# Duckietown_2018B.net
KiCad netlist of a schematic drawn in EAGLE
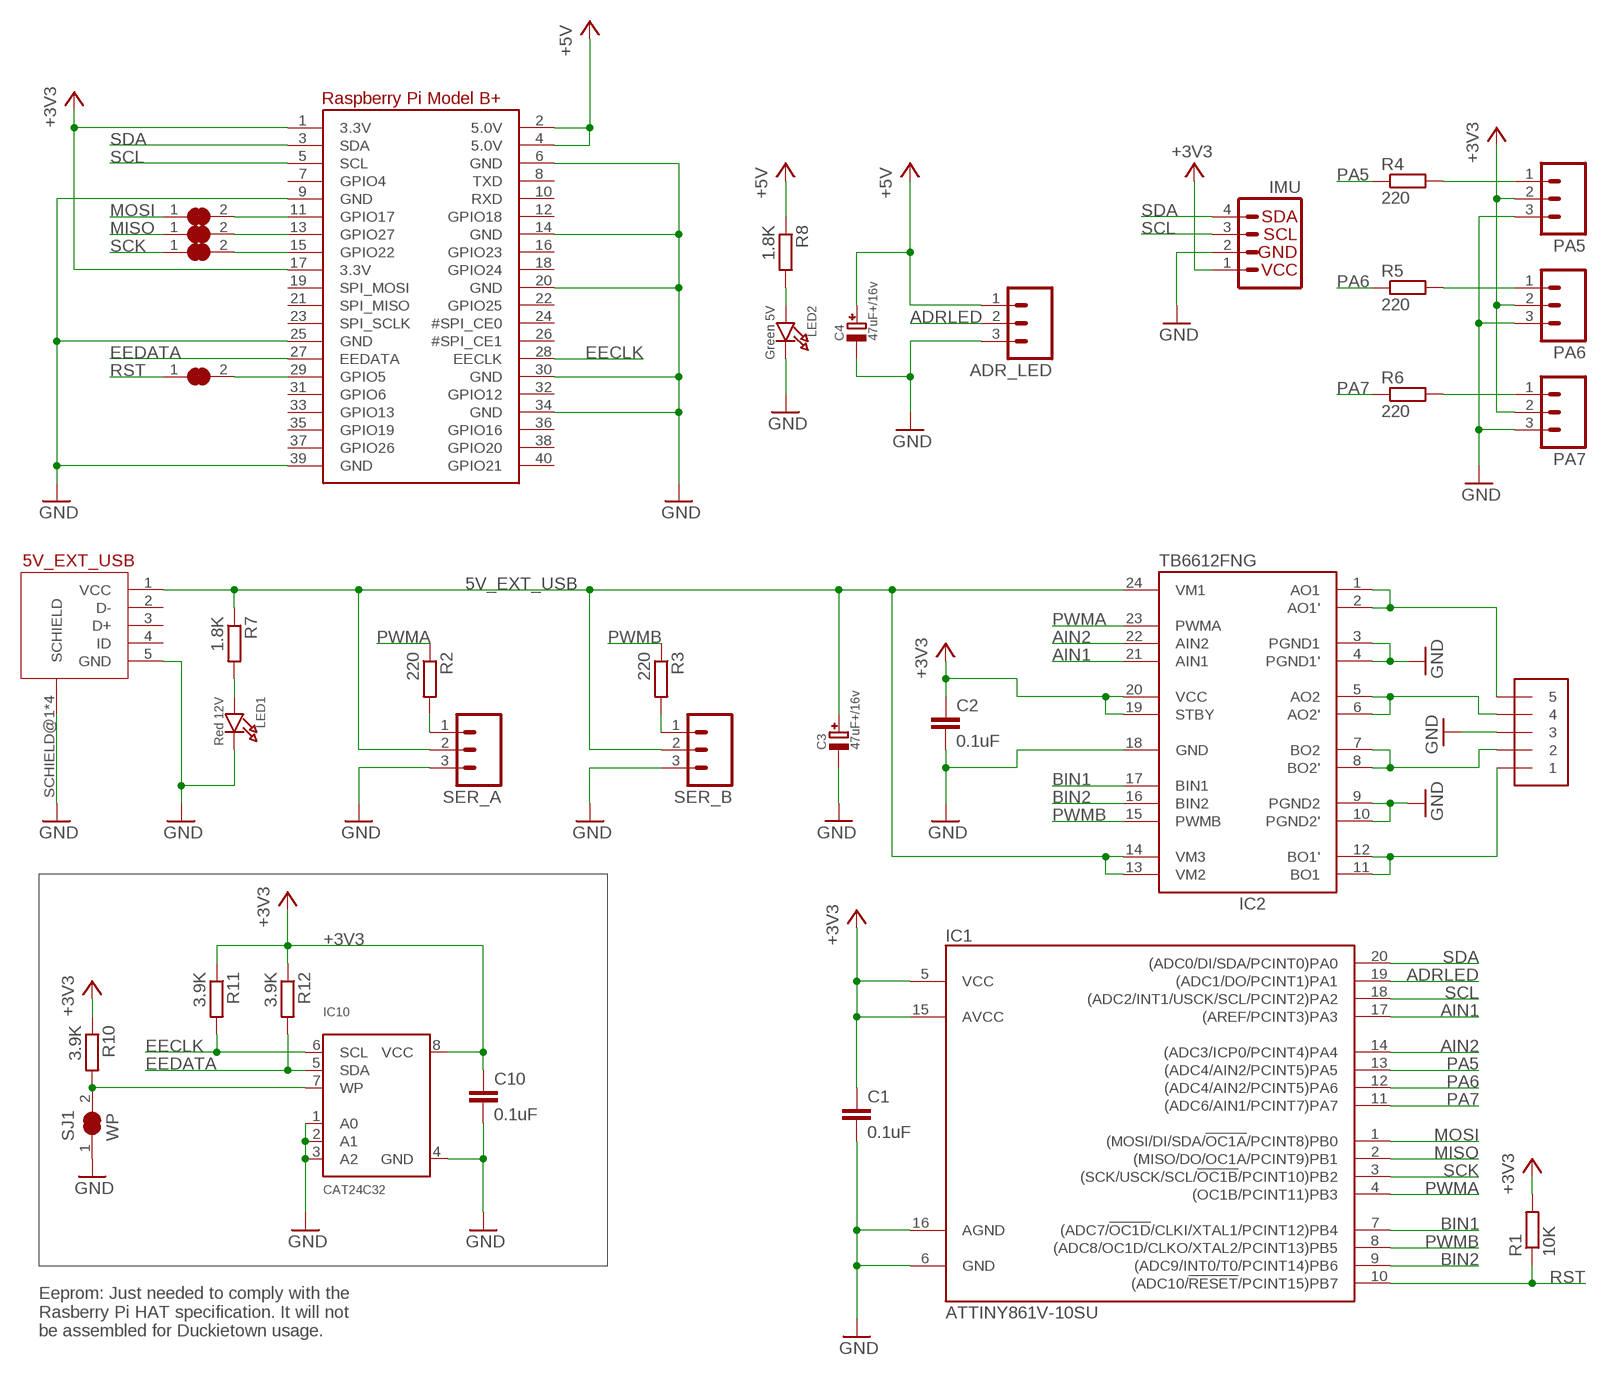
[diagram p0: schematic, sheet 1]

(export (version "E")
  (design (tool "Eeschema 10.0.6"))
  (components
    (comp (ref "5V_EXT_USB")
      (value "MICROUSBCON")
      (footprint "eagle-import:MICROUSBCON")
      (libsource (lib "eagle-import") (part "MICROUSBCON"))
    )
    (comp (ref "ADR_LED")
      (value "M03PTH")
      (footprint "eagle-import:1X03")
      (libsource (lib "eagle-import") (part "M03PTH"))
    )
    (comp (ref "C1")
      (value "0.1uF")
      (footprint "eagle-import:C0603")
      (libsource (lib "eagle-import") (part "C-EUC0603"))
    )
    (comp (ref "C2")
      (value "0.1uF")
      (footprint "eagle-import:C0603")
      (libsource (lib "eagle-import") (part "C-EUC0603"))
    )
    (comp (ref "C3")
      (value "47uF+/16v")
      (footprint "eagle-import:PANASONIC_C")
      (libsource (lib "eagle-import") (part "CAP_ELECTROLYTICPANASONIC_C"))
    )
    (comp (ref "C4")
      (value "47uF+/16v")
      (footprint "eagle-import:PANASONIC_C")
      (libsource (lib "eagle-import") (part "CAP_ELECTROLYTICPANASONIC_C"))
    )
    (comp (ref "C10")
      (value "0.1uF")
      (footprint "eagle-import:C0603")
      (libsource (lib "eagle-import") (part "C-EUC0603"))
    )
    (comp (ref "IC1")
      (value "ATTINY861V-10SU")
      (footprint "eagle-import:SO20L")
      (libsource (lib "eagle-import") (part "ATTINY861V-10SU"))
    )
    (comp (ref "IC2")
      (value "TB6612FNG")
      (footprint "eagle-import:SSOP24")
      (libsource (lib "eagle-import") (part "TB6612FNG"))
    )
    (comp (ref "IC10")
      (value "CAT24C32")
      (footprint "eagle-import:SOIC8_150MIL")
      (libsource (lib "eagle-import") (part "EEPROM_I2C_SOIC8_GENERIC"))
    )
    (comp (ref "IMU")
      (value "I2C_IMU_L3GD20H+LSM303")
      (footprint "eagle-import:1X04")
      (libsource (lib "eagle-import") (part "I2C_IMU_L3GD20H+LSM303"))
    )
    (comp (ref "LED1")
      (value "Red 12V")
      (footprint "eagle-import:CHIPLED_0805_NOOUTLINE")
      (libsource (lib "eagle-import") (part "LED0805_NOOUTLINE"))
    )
    (comp (ref "LED2")
      (value "Green 5V")
      (footprint "eagle-import:CHIPLED_0805_NOOUTLINE")
      (libsource (lib "eagle-import") (part "LED0805_NOOUTLINE"))
    )
    (comp (ref "MOTA")
      (value "1X5")
      (footprint "eagle-import:1X05-3.5MM")
      (libsource (lib "eagle-import") (part "1X5"))
    )
    (comp (ref "PA5")
      (value "M03PTH")
      (footprint "eagle-import:1X03")
      (libsource (lib "eagle-import") (part "M03PTH"))
    )
    (comp (ref "PA6")
      (value "M03PTH")
      (footprint "eagle-import:1X03")
      (libsource (lib "eagle-import") (part "M03PTH"))
    )
    (comp (ref "PA7")
      (value "M03PTH")
      (footprint "eagle-import:1X03")
      (libsource (lib "eagle-import") (part "M03PTH"))
    )
    (comp (ref "R1")
      (value "10K")
      (footprint "eagle-import:R0603")
      (libsource (lib "eagle-import") (part "R-EU_R0603"))
    )
    (comp (ref "R2")
      (value "220")
      (footprint "eagle-import:R0603")
      (libsource (lib "eagle-import") (part "R-EU_R0603"))
    )
    (comp (ref "R3")
      (value "220")
      (footprint "eagle-import:R0603")
      (libsource (lib "eagle-import") (part "R-EU_R0603"))
    )
    (comp (ref "R4")
      (value "220")
      (footprint "eagle-import:R0603")
      (libsource (lib "eagle-import") (part "R-EU_R0603"))
    )
    (comp (ref "R5")
      (value "220")
      (footprint "eagle-import:R0603")
      (libsource (lib "eagle-import") (part "R-EU_R0603"))
    )
    (comp (ref "R6")
      (value "220")
      (footprint "eagle-import:R0603")
      (libsource (lib "eagle-import") (part "R-EU_R0603"))
    )
    (comp (ref "R7")
      (value "1.8K")
      (footprint "eagle-import:R0603")
      (libsource (lib "eagle-import") (part "R-EU_R0603"))
    )
    (comp (ref "R8")
      (value "1.8K")
      (footprint "eagle-import:R0603")
      (libsource (lib "eagle-import") (part "R-EU_R0603"))
    )
    (comp (ref "R10")
      (value "3.9K")
      (footprint "eagle-import:R0603")
      (libsource (lib "eagle-import") (part "R-EU_R0603"))
    )
    (comp (ref "R11")
      (value "3.9K")
      (footprint "eagle-import:R0603")
      (libsource (lib "eagle-import") (part "R-EU_R0603"))
    )
    (comp (ref "R12")
      (value "3.9K")
      (footprint "eagle-import:R0603")
      (libsource (lib "eagle-import") (part "R-EU_R0603"))
    )
    (comp (ref "RPI2")
      (value "RASPBERRYPI_BPLUS_HATSLOTS")
      (footprint "eagle-import:PI_HAT_SLOTS")
      (libsource (lib "eagle-import") (part "RASPBERRYPI_BPLUS_HATSLOTS"))
    )
    (comp (ref "RP_MISO")
      (value "SOLDERJUMPER_CLOSED")
      (footprint "eagle-import:SOLDERJUMPER_CLOSEDWIRE")
      (libsource (lib "eagle-import") (part "SOLDERJUMPER_CLOSED"))
    )
    (comp (ref "RP_MOSI")
      (value "SOLDERJUMPER_CLOSED")
      (footprint "eagle-import:SOLDERJUMPER_CLOSEDWIRE")
      (libsource (lib "eagle-import") (part "SOLDERJUMPER_CLOSED"))
    )
    (comp (ref "RP_RST")
      (value "SOLDERJUMPER_CLOSED")
      (footprint "eagle-import:SOLDERJUMPER_CLOSEDWIRE")
      (libsource (lib "eagle-import") (part "SOLDERJUMPER_CLOSED"))
    )
    (comp (ref "RP_SCK")
      (value "SOLDERJUMPER_CLOSED")
      (footprint "eagle-import:SOLDERJUMPER_CLOSEDWIRE")
      (libsource (lib "eagle-import") (part "SOLDERJUMPER_CLOSED"))
    )
    (comp (ref "SER_A")
      (value "M03PTH")
      (footprint "eagle-import:1X03")
      (libsource (lib "eagle-import") (part "M03PTH"))
    )
    (comp (ref "SER_B")
      (value "M03PTH")
      (footprint "eagle-import:1X03")
      (libsource (lib "eagle-import") (part "M03PTH"))
    )
    (comp (ref "SJ1")
      (value "WP")
      (footprint "eagle-import:SOLDERJUMPER_CLOSEDWIRE")
      (libsource (lib "eagle-import") (part "SOLDERJUMPER_CLOSED"))
    )
  )
  (nets
    (net (code "1") (name "+3V3") (class "Default")
      (node (ref "C1") (pin "1") (pinfunction "1_1") (pintype "passive"))
      (node (ref "C10") (pin "1") (pinfunction "1_1") (pintype "passive"))
      (node (ref "C2") (pin "1") (pinfunction "1_1") (pintype "passive"))
      (node (ref "IC1") (pin "15") (pinfunction "AVCC_15") (pintype "power_in"))
      (node (ref "IC1") (pin "5") (pinfunction "VCC_5") (pintype "power_in"))
      (node (ref "IC10") (pin "8") (pinfunction "VCC_8") (pintype "power_in"))
      (node (ref "IC2") (pin "19") (pinfunction "STBY_19") (pintype "input"))
      (node (ref "IC2") (pin "20") (pinfunction "VCC_20") (pintype "power_in"))
      (node (ref "IMU") (pin "1") (pinfunction "1_1") (pintype "passive"))
      (node (ref "PA5") (pin "2") (pinfunction "2_2") (pintype "passive"))
      (node (ref "PA6") (pin "2") (pinfunction "2_2") (pintype "passive"))
      (node (ref "PA7") (pin "2") (pinfunction "2_2") (pintype "passive"))
      (node (ref "R1") (pin "2") (pinfunction "2_2") (pintype "passive"))
      (node (ref "R10") (pin "1") (pinfunction "1_1") (pintype "passive"))
      (node (ref "R11") (pin "1") (pinfunction "1_1") (pintype "passive"))
      (node (ref "R12") (pin "1") (pinfunction "1_1") (pintype "passive"))
      (node (ref "RPI2") (pin "1") (pinfunction "3.3V_1") (pintype "power_in"))
      (node (ref "RPI2") (pin "17") (pinfunction "3.3V_17") (pintype "power_in"))
    )
    (net (code "2") (name "+5V") (class "Default")
      (node (ref "ADR_LED") (pin "1") (pinfunction "1_1") (pintype "passive"))
      (node (ref "C4") (pin "+") (pinfunction "+_+") (pintype "passive"))
      (node (ref "R8") (pin "1") (pinfunction "1_1") (pintype "passive"))
      (node (ref "RPI2") (pin "2") (pinfunction "5.0V_2") (pintype "power_in"))
      (node (ref "RPI2") (pin "4") (pinfunction "5.0V_4") (pintype "power_in"))
    )
    (net (code "3") (name "/5V_EXT_USB") (class "Default")
      (node (ref "5V_EXT_USB") (pin "1") (pinfunction "VCC_1") (pintype "power_in"))
      (node (ref "C3") (pin "+") (pinfunction "+_+") (pintype "passive"))
      (node (ref "IC2") (pin "13") (pinfunction "VM2_13") (pintype "power_in"))
      (node (ref "IC2") (pin "14") (pinfunction "VM3_14") (pintype "power_in"))
      (node (ref "IC2") (pin "24") (pinfunction "VM1_24") (pintype "power_in"))
      (node (ref "R7") (pin "1") (pinfunction "1_1") (pintype "passive"))
      (node (ref "SER_A") (pin "2") (pinfunction "2_2") (pintype "passive"))
      (node (ref "SER_B") (pin "2") (pinfunction "2_2") (pintype "passive"))
    )
    (net (code "4") (name "/ADRLED") (class "Default")
      (node (ref "ADR_LED") (pin "2") (pinfunction "2_2") (pintype "passive"))
      (node (ref "IC1") (pin "19") (pinfunction "(ADC1/DO/PCINT1)PA1_19") (pintype "bidirectional"))
    )
    (net (code "5") (name "/AIN1") (class "Default")
      (node (ref "IC1") (pin "17") (pinfunction "(AREF/PCINT3)PA3_17") (pintype "bidirectional"))
      (node (ref "IC2") (pin "21") (pinfunction "AIN1_21") (pintype "input"))
    )
    (net (code "6") (name "/AIN2") (class "Default")
      (node (ref "IC1") (pin "14") (pinfunction "(ADC3/ICP0/PCINT4)PA4_14") (pintype "bidirectional"))
      (node (ref "IC2") (pin "22") (pinfunction "AIN2_22") (pintype "input"))
    )
    (net (code "7") (name "/BIN1") (class "Default")
      (node (ref "IC1") (pin "7") (pinfunction "(ADC7/~{OC1D}/CLKI/XTAL1/PCINT12)PB4_7") (pintype "bidirectional"))
      (node (ref "IC2") (pin "17") (pinfunction "BIN1_17") (pintype "input"))
    )
    (net (code "8") (name "/BIN2") (class "Default")
      (node (ref "IC1") (pin "9") (pinfunction "(ADC9/INT0/T0/PCINT14)PB6_9") (pintype "bidirectional"))
      (node (ref "IC2") (pin "16") (pinfunction "BIN2_16") (pintype "input"))
    )
    (net (code "9") (name "/EECLK") (class "Default")
      (node (ref "IC10") (pin "6") (pinfunction "SCL_6") (pintype "input"))
      (node (ref "R11") (pin "2") (pinfunction "2_2") (pintype "passive"))
      (node (ref "RPI2") (pin "28") (pinfunction "EECLK_28") (pintype "power_in"))
    )
    (net (code "10") (name "/EEDATA") (class "Default")
      (node (ref "IC10") (pin "5") (pinfunction "SDA_5") (pintype "bidirectional"))
      (node (ref "R12") (pin "2") (pinfunction "2_2") (pintype "passive"))
      (node (ref "RPI2") (pin "27") (pinfunction "EEDATA_27") (pintype "bidirectional"))
    )
    (net (code "11") (name "/GPIO6") (class "Default")
      (node (ref "RPI2") (pin "31") (pinfunction "GPIO6_31") (pintype "power_in"))
    )
    (net (code "12") (name "/GPIO16") (class "Default")
      (node (ref "RPI2") (pin "36") (pinfunction "GPIO16_36") (pintype "power_in"))
    )
    (net (code "13") (name "/MISO") (class "Default")
      (node (ref "IC1") (pin "2") (pinfunction "(MISO/DO/OC1A/PCINT9)PB1_2") (pintype "bidirectional"))
      (node (ref "RP_MISO") (pin "1") (pinfunction "1_1") (pintype "passive"))
    )
    (net (code "14") (name "/MOSI") (class "Default")
      (node (ref "IC1") (pin "1") (pinfunction "(MOSI/DI/SDA/~{OC1A}/PCINT8)PB0_1") (pintype "bidirectional"))
      (node (ref "RP_MOSI") (pin "1") (pinfunction "1_1") (pintype "passive"))
    )
    (net (code "15") (name "/PA5") (class "Default")
      (node (ref "IC1") (pin "13") (pinfunction "(ADC4/AIN2/PCINT5)PA5_13") (pintype "bidirectional"))
      (node (ref "R4") (pin "1") (pinfunction "1_1") (pintype "passive"))
    )
    (net (code "16") (name "/PA6") (class "Default")
      (node (ref "IC1") (pin "12") (pinfunction "(ADC4/AIN2/PCINT5)PA6_12") (pintype "bidirectional"))
      (node (ref "R5") (pin "1") (pinfunction "1_1") (pintype "passive"))
    )
    (net (code "17") (name "/PA7") (class "Default")
      (node (ref "IC1") (pin "11") (pinfunction "(ADC6/AIN1/PCINT7)PA7_11") (pintype "bidirectional"))
      (node (ref "R6") (pin "1") (pinfunction "1_1") (pintype "passive"))
    )
    (net (code "18") (name "/PWMA") (class "Default")
      (node (ref "IC1") (pin "4") (pinfunction "(OC1B/PCINT11)PB3_4") (pintype "bidirectional"))
      (node (ref "IC2") (pin "23") (pinfunction "PWMA_23") (pintype "input"))
      (node (ref "R2") (pin "1") (pinfunction "1_1") (pintype "passive"))
    )
    (net (code "19") (name "/PWMB") (class "Default")
      (node (ref "IC1") (pin "8") (pinfunction "(ADC8/OC1D/CLKO/XTAL2/PCINT13)PB5_8") (pintype "bidirectional"))
      (node (ref "IC2") (pin "15") (pinfunction "PWMB_15") (pintype "input"))
      (node (ref "R3") (pin "1") (pinfunction "1_1") (pintype "passive"))
    )
    (net (code "20") (name "/RST") (class "Default")
      (node (ref "IC1") (pin "10") (pinfunction "(ADC10/~{RESET}/PCINT15)PB7_10") (pintype "bidirectional"))
      (node (ref "R1") (pin "1") (pinfunction "1_1") (pintype "passive"))
      (node (ref "RP_RST") (pin "1") (pinfunction "1_1") (pintype "passive"))
    )
    (net (code "21") (name "/SCK") (class "Default")
      (node (ref "IC1") (pin "3") (pinfunction "(SCK/USCK/SCL/~{OC1B}/PCINT10)PB2_3") (pintype "bidirectional"))
      (node (ref "RP_SCK") (pin "1") (pinfunction "1_1") (pintype "passive"))
    )
    (net (code "22") (name "/SCL") (class "Default")
      (node (ref "IC1") (pin "18") (pinfunction "(ADC2/INT1/USCK/SCL/PCINT2)PA2_18") (pintype "bidirectional"))
      (node (ref "IMU") (pin "3") (pinfunction "3_3") (pintype "passive"))
      (node (ref "RPI2") (pin "5") (pinfunction "SCL_5") (pintype "bidirectional"))
    )
    (net (code "23") (name "/SDA") (class "Default")
      (node (ref "IC1") (pin "20") (pinfunction "(ADC0/DI/SDA/PCINT0)PA0_20") (pintype "bidirectional"))
      (node (ref "IMU") (pin "4") (pinfunction "4_4") (pintype "passive"))
      (node (ref "RPI2") (pin "3") (pinfunction "SDA_3") (pintype "bidirectional"))
    )
    (net (code "24") (name "GND") (class "Default")
      (node (ref "5V_EXT_USB") (pin "5") (pinfunction "GND_5") (pintype "power_in"))
      (node (ref "5V_EXT_USB") (pin "SCHIELD@1") (pinfunction "SCHIELD_SCHIELD@1") (pintype "bidirectional"))
      (node (ref "5V_EXT_USB") (pin "SCHIELD@2") (pinfunction "SCHIELD_SCHIELD@2") (pintype "bidirectional"))
      (node (ref "5V_EXT_USB") (pin "SCHIELD@3") (pinfunction "SCHIELD_SCHIELD@3") (pintype "bidirectional"))
      (node (ref "5V_EXT_USB") (pin "SCHIELD@4") (pinfunction "SCHIELD_SCHIELD@4") (pintype "bidirectional"))
      (node (ref "ADR_LED") (pin "3") (pinfunction "3_3") (pintype "passive"))
      (node (ref "C1") (pin "2") (pinfunction "2_2") (pintype "passive"))
      (node (ref "C10") (pin "2") (pinfunction "2_2") (pintype "passive"))
      (node (ref "C2") (pin "2") (pinfunction "2_2") (pintype "passive"))
      (node (ref "C3") (pin "-") (pinfunction "-_-") (pintype "passive"))
      (node (ref "C4") (pin "-") (pinfunction "-_-") (pintype "passive"))
      (node (ref "IC1") (pin "16") (pinfunction "AGND_16") (pintype "power_in"))
      (node (ref "IC1") (pin "6") (pinfunction "GND_6") (pintype "power_in"))
      (node (ref "IC10") (pin "1") (pinfunction "A0_1") (pintype "input"))
      (node (ref "IC10") (pin "2") (pinfunction "A1_2") (pintype "input"))
      (node (ref "IC10") (pin "3") (pinfunction "A2_3") (pintype "input"))
      (node (ref "IC10") (pin "4") (pinfunction "GND_4") (pintype "power_in"))
      (node (ref "IC2") (pin "10") (pinfunction "PGND2'_10") (pintype "power_in"))
      (node (ref "IC2") (pin "18") (pinfunction "GND_18") (pintype "power_in"))
      (node (ref "IC2") (pin "3") (pinfunction "PGND1_3") (pintype "power_in"))
      (node (ref "IC2") (pin "4") (pinfunction "PGND1'_4") (pintype "power_in"))
      (node (ref "IC2") (pin "9") (pinfunction "PGND2_9") (pintype "power_in"))
      (node (ref "IMU") (pin "2") (pinfunction "2_2") (pintype "passive"))
      (node (ref "LED1") (pin "C") (pinfunction "C_C") (pintype "passive"))
      (node (ref "LED2") (pin "C") (pinfunction "C_C") (pintype "passive"))
      (node (ref "MOTA") (pin "3") (pinfunction "3_3") (pintype "passive"))
      (node (ref "PA5") (pin "3") (pinfunction "3_3") (pintype "passive"))
      (node (ref "PA6") (pin "3") (pinfunction "3_3") (pintype "passive"))
      (node (ref "PA7") (pin "3") (pinfunction "3_3") (pintype "passive"))
      (node (ref "RPI2") (pin "14") (pinfunction "GND_14") (pintype "power_in"))
      (node (ref "RPI2") (pin "20") (pinfunction "GND_20") (pintype "power_in"))
      (node (ref "RPI2") (pin "25") (pinfunction "GND_25") (pintype "power_in"))
      (node (ref "RPI2") (pin "30") (pinfunction "GND_30") (pintype "bidirectional"))
      (node (ref "RPI2") (pin "34") (pinfunction "GND_34") (pintype "bidirectional"))
      (node (ref "RPI2") (pin "39") (pinfunction "GND_39") (pintype "power_in"))
      (node (ref "RPI2") (pin "6") (pinfunction "GND_6") (pintype "power_in"))
      (node (ref "RPI2") (pin "9") (pinfunction "GND_9") (pintype "power_in"))
      (node (ref "SER_A") (pin "3") (pinfunction "3_3") (pintype "passive"))
      (node (ref "SER_B") (pin "3") (pinfunction "3_3") (pintype "passive"))
      (node (ref "SJ1") (pin "1") (pinfunction "1_1") (pintype "passive"))
    )
    (net (code "25") (name "Net-(IC2-AO1')") (class "Default")
      (node (ref "IC2") (pin "1") (pinfunction "AO1_1") (pintype "output"))
      (node (ref "IC2") (pin "2") (pinfunction "AO1'_2") (pintype "output"))
      (node (ref "MOTA") (pin "5") (pinfunction "5_5") (pintype "passive"))
    )
    (net (code "26") (name "Net-(IC2-AO2')") (class "Default")
      (node (ref "IC2") (pin "5") (pinfunction "AO2_5") (pintype "output"))
      (node (ref "IC2") (pin "6") (pinfunction "AO2'_6") (pintype "output"))
      (node (ref "MOTA") (pin "4") (pinfunction "4_4") (pintype "passive"))
    )
    (net (code "27") (name "Net-(IC2-BO1')") (class "Default")
      (node (ref "IC2") (pin "11") (pinfunction "BO1_11") (pintype "output"))
      (node (ref "IC2") (pin "12") (pinfunction "BO1'_12") (pintype "output"))
      (node (ref "MOTA") (pin "1") (pinfunction "1_1") (pintype "passive"))
    )
    (net (code "28") (name "Net-(IC2-BO2')") (class "Default")
      (node (ref "IC2") (pin "7") (pinfunction "BO2_7") (pintype "output"))
      (node (ref "IC2") (pin "8") (pinfunction "BO2'_8") (pintype "output"))
      (node (ref "MOTA") (pin "2") (pinfunction "2_2") (pintype "passive"))
    )
    (net (code "29") (name "Net-(IC10-WP)") (class "Default")
      (node (ref "IC10") (pin "7") (pinfunction "WP_7") (pintype "input"))
      (node (ref "R10") (pin "2") (pinfunction "2_2") (pintype "passive"))
      (node (ref "SJ1") (pin "2") (pinfunction "2_2") (pintype "passive"))
    )
    (net (code "30") (name "Net-(LED1-PadA)") (class "Default")
      (node (ref "LED1") (pin "A") (pinfunction "A_A") (pintype "passive"))
      (node (ref "R7") (pin "2") (pinfunction "2_2") (pintype "passive"))
    )
    (net (code "31") (name "Net-(LED2-PadA)") (class "Default")
      (node (ref "LED2") (pin "A") (pinfunction "A_A") (pintype "passive"))
      (node (ref "R8") (pin "2") (pinfunction "2_2") (pintype "passive"))
    )
    (net (code "32") (name "Net-(PA5-Pad1)") (class "Default")
      (node (ref "PA5") (pin "1") (pinfunction "1_1") (pintype "passive"))
      (node (ref "R4") (pin "2") (pinfunction "2_2") (pintype "passive"))
    )
    (net (code "33") (name "Net-(PA6-Pad1)") (class "Default")
      (node (ref "PA6") (pin "1") (pinfunction "1_1") (pintype "passive"))
      (node (ref "R5") (pin "2") (pinfunction "2_2") (pintype "passive"))
    )
    (net (code "34") (name "Net-(PA7-Pad1)") (class "Default")
      (node (ref "PA7") (pin "1") (pinfunction "1_1") (pintype "passive"))
      (node (ref "R6") (pin "2") (pinfunction "2_2") (pintype "passive"))
    )
    (net (code "35") (name "Net-(R2-Pad2)") (class "Default")
      (node (ref "R2") (pin "2") (pinfunction "2_2") (pintype "passive"))
      (node (ref "SER_A") (pin "1") (pinfunction "1_1") (pintype "passive"))
    )
    (net (code "36") (name "Net-(R3-Pad2)") (class "Default")
      (node (ref "R3") (pin "2") (pinfunction "2_2") (pintype "passive"))
      (node (ref "SER_B") (pin "1") (pinfunction "1_1") (pintype "passive"))
    )
    (net (code "37") (name "Net-(RPI2-GPIO5)") (class "Default")
      (node (ref "RPI2") (pin "29") (pinfunction "GPIO5_29") (pintype "bidirectional"))
      (node (ref "RP_RST") (pin "2") (pinfunction "2_2") (pintype "passive"))
    )
    (net (code "38") (name "Net-(RPI2-GPIO17)") (class "Default")
      (node (ref "RPI2") (pin "11") (pinfunction "GPIO17_11") (pintype "bidirectional"))
      (node (ref "RP_MOSI") (pin "2") (pinfunction "2_2") (pintype "passive"))
    )
    (net (code "39") (name "Net-(RPI2-GPIO22)") (class "Default")
      (node (ref "RPI2") (pin "15") (pinfunction "GPIO22_15") (pintype "bidirectional"))
      (node (ref "RP_SCK") (pin "2") (pinfunction "2_2") (pintype "passive"))
    )
    (net (code "40") (name "Net-(RPI2-GPIO27)") (class "Default")
      (node (ref "RPI2") (pin "13") (pinfunction "GPIO27_13") (pintype "bidirectional"))
      (node (ref "RP_MISO") (pin "2") (pinfunction "2_2") (pintype "passive"))
    )
    (net (code "41") (name "unconnected-(5V_EXT_USB-D+-Pad3)") (class "Default")
      (node (ref "5V_EXT_USB") (pin "3") (pinfunction "D+_3") (pintype "bidirectional"))
    )
    (net (code "42") (name "unconnected-(5V_EXT_USB-D--Pad2)") (class "Default")
      (node (ref "5V_EXT_USB") (pin "2") (pinfunction "D-_2") (pintype "bidirectional"))
    )
    (net (code "43") (name "unconnected-(5V_EXT_USB-ID-Pad4)") (class "Default")
      (node (ref "5V_EXT_USB") (pin "4") (pinfunction "ID_4") (pintype "bidirectional"))
    )
    (net (code "44") (name "unconnected-(RPI2-#SPI_CE0-Pad24)") (class "Default")
      (node (ref "RPI2") (pin "24") (pinfunction "#SPI_CE0_24") (pintype "bidirectional"))
    )
    (net (code "45") (name "unconnected-(RPI2-#SPI_CE1-Pad26)") (class "Default")
      (node (ref "RPI2") (pin "26") (pinfunction "#SPI_CE1_26") (pintype "bidirectional"))
    )
    (net (code "46") (name "unconnected-(RPI2-GPIO4-Pad7)") (class "Default")
      (node (ref "RPI2") (pin "7") (pinfunction "GPIO4_7") (pintype "bidirectional"))
    )
    (net (code "47") (name "unconnected-(RPI2-GPIO12-Pad32)") (class "Default")
      (node (ref "RPI2") (pin "32") (pinfunction "GPIO12_32") (pintype "bidirectional"))
    )
    (net (code "48") (name "unconnected-(RPI2-GPIO13-Pad33)") (class "Default")
      (node (ref "RPI2") (pin "33") (pinfunction "GPIO13_33") (pintype "bidirectional"))
    )
    (net (code "49") (name "unconnected-(RPI2-GPIO18-Pad12)") (class "Default")
      (node (ref "RPI2") (pin "12") (pinfunction "GPIO18_12") (pintype "bidirectional"))
    )
    (net (code "50") (name "unconnected-(RPI2-GPIO19-Pad35)") (class "Default")
      (node (ref "RPI2") (pin "35") (pinfunction "GPIO19_35") (pintype "bidirectional"))
    )
    (net (code "51") (name "unconnected-(RPI2-GPIO20-Pad38)") (class "Default")
      (node (ref "RPI2") (pin "38") (pinfunction "GPIO20_38") (pintype "bidirectional"))
    )
    (net (code "52") (name "unconnected-(RPI2-GPIO21-Pad40)") (class "Default")
      (node (ref "RPI2") (pin "40") (pinfunction "GPIO21_40") (pintype "bidirectional"))
    )
    (net (code "53") (name "unconnected-(RPI2-GPIO23-Pad16)") (class "Default")
      (node (ref "RPI2") (pin "16") (pinfunction "GPIO23_16") (pintype "bidirectional"))
    )
    (net (code "54") (name "unconnected-(RPI2-GPIO24-Pad18)") (class "Default")
      (node (ref "RPI2") (pin "18") (pinfunction "GPIO24_18") (pintype "bidirectional"))
    )
    (net (code "55") (name "unconnected-(RPI2-GPIO25-Pad22)") (class "Default")
      (node (ref "RPI2") (pin "22") (pinfunction "GPIO25_22") (pintype "bidirectional"))
    )
    (net (code "56") (name "unconnected-(RPI2-GPIO26-Pad37)") (class "Default")
      (node (ref "RPI2") (pin "37") (pinfunction "GPIO26_37") (pintype "bidirectional"))
    )
    (net (code "57") (name "unconnected-(RPI2-RXD-Pad10)") (class "Default")
      (node (ref "RPI2") (pin "10") (pinfunction "RXD_10") (pintype "bidirectional"))
    )
    (net (code "58") (name "unconnected-(RPI2-SPI_MISO-Pad21)") (class "Default")
      (node (ref "RPI2") (pin "21") (pinfunction "SPI_MISO_21") (pintype "bidirectional"))
    )
    (net (code "59") (name "unconnected-(RPI2-SPI_MOSI-Pad19)") (class "Default")
      (node (ref "RPI2") (pin "19") (pinfunction "SPI_MOSI_19") (pintype "bidirectional"))
    )
    (net (code "60") (name "unconnected-(RPI2-SPI_SCLK-Pad23)") (class "Default")
      (node (ref "RPI2") (pin "23") (pinfunction "SPI_SCLK_23") (pintype "bidirectional"))
    )
    (net (code "61") (name "unconnected-(RPI2-TXD-Pad8)") (class "Default")
      (node (ref "RPI2") (pin "8") (pinfunction "TXD_8") (pintype "output"))
    )
  )
)
